# M_H_ext_disp.net
KiCad netlist of a schematic drawn in EAGLE
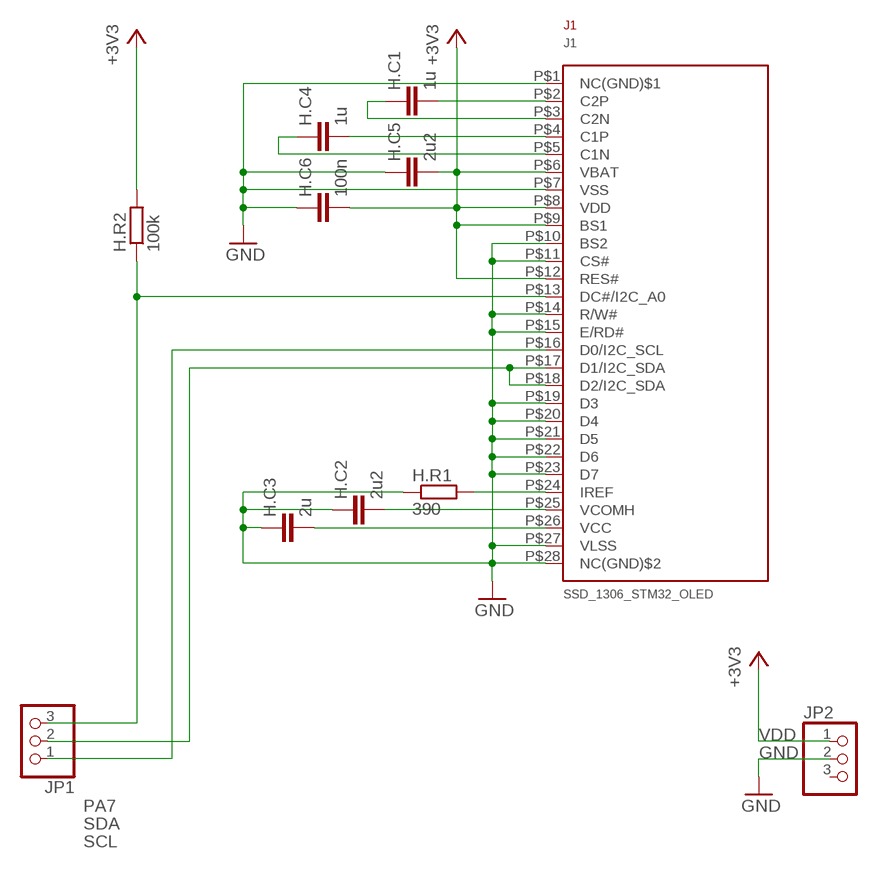
[diagram p0: schematic, sheet 1]

(export (version "E")
  (design (tool "Eeschema 10.0.6"))
  (components
    (comp (ref "H.C1")
      (value "1u")
      (footprint "eagle-import:C0603")
      (libsource (lib "eagle-import") (part "C-EUC0603"))
    )
    (comp (ref "H.C2")
      (value "2u2")
      (footprint "eagle-import:C0603")
      (libsource (lib "eagle-import") (part "C-EUC0603"))
    )
    (comp (ref "H.C3")
      (value "2u")
      (footprint "eagle-import:C0603")
      (libsource (lib "eagle-import") (part "C-EUC0603"))
    )
    (comp (ref "H.C4")
      (value "1u")
      (footprint "eagle-import:C0603")
      (libsource (lib "eagle-import") (part "C-EUC0603"))
    )
    (comp (ref "H.C5")
      (value "2u2")
      (footprint "eagle-import:C0603")
      (libsource (lib "eagle-import") (part "C-EUC0603"))
    )
    (comp (ref "H.C6")
      (value "100n")
      (footprint "eagle-import:C0603")
      (libsource (lib "eagle-import") (part "C-EUC0603"))
    )
    (comp (ref "H.R1")
      (value "390")
      (footprint "eagle-import:R0603")
      (libsource (lib "eagle-import") (part "R-EU_R0603"))
    )
    (comp (ref "H.R2")
      (value "100k")
      (footprint "eagle-import:R0603")
      (libsource (lib "eagle-import") (part "R-EU_R0603"))
    )
    (comp (ref "J1")
      (value "SSD_1306_STM32_OLED")
      (footprint "eagle-import:SSD_1306_STM32_OLED")
      (libsource (lib "eagle-import") (part "SSD_1306_STM32_OLED"))
    )
    (comp (ref "JP1")
      (value "PINHD-1X3")
      (footprint "eagle-import:1X03")
      (libsource (lib "eagle-import") (part "PINHD-1X3"))
    )
    (comp (ref "JP2")
      (value "PINHD-1X3")
      (footprint "eagle-import:1X03")
      (libsource (lib "eagle-import") (part "PINHD-1X3"))
    )
  )
  (nets
    (net (code "1") (name "+3V3") (class "Default")
      (node (ref "H.C5") (pin "2") (pinfunction "2_2") (pintype "passive"))
      (node (ref "H.C6") (pin "2") (pinfunction "2_2") (pintype "passive"))
      (node (ref "H.R2") (pin "2") (pinfunction "2_2") (pintype "passive"))
      (node (ref "J1") (pin "P$12") (pinfunction "RES#_P$12") (pintype "input"))
      (node (ref "J1") (pin "P$6") (pinfunction "VBAT_P$6") (pintype "input"))
      (node (ref "J1") (pin "P$8") (pinfunction "VDD_P$8") (pintype "power_in"))
      (node (ref "J1") (pin "P$9") (pinfunction "BS1_P$9") (pintype "input"))
      (node (ref "JP2") (pin "1") (pinfunction "1_1") (pintype "passive"))
    )
    (net (code "2") (name "/PA7") (class "Default")
      (node (ref "H.R2") (pin "1") (pinfunction "1_1") (pintype "passive"))
      (node (ref "J1") (pin "P$13") (pinfunction "DC#/I2C_A0_P$13") (pintype "input"))
      (node (ref "JP1") (pin "3") (pinfunction "3_3") (pintype "passive"))
    )
    (net (code "3") (name "/SCL") (class "Default")
      (node (ref "J1") (pin "P$16") (pinfunction "D0/I2C_SCL_P$16") (pintype "bidirectional"))
      (node (ref "JP1") (pin "1") (pinfunction "1_1") (pintype "passive"))
    )
    (net (code "4") (name "/SDA") (class "Default")
      (node (ref "J1") (pin "P$17") (pinfunction "D1/I2C_SDA_P$17") (pintype "bidirectional"))
      (node (ref "J1") (pin "P$18") (pinfunction "D2/I2C_SDA_P$18") (pintype "bidirectional"))
      (node (ref "JP1") (pin "2") (pinfunction "2_2") (pintype "passive"))
    )
    (net (code "5") (name "GND") (class "Default")
      (node (ref "H.C2") (pin "1") (pinfunction "1_1") (pintype "passive"))
      (node (ref "H.C3") (pin "1") (pinfunction "1_1") (pintype "passive"))
      (node (ref "H.C5") (pin "1") (pinfunction "1_1") (pintype "passive"))
      (node (ref "H.C6") (pin "1") (pinfunction "1_1") (pintype "passive"))
      (node (ref "H.R1") (pin "1") (pinfunction "1_1") (pintype "passive"))
      (node (ref "J1") (pin "P$1") (pinfunction "NC(GND)$1_P$1") (pintype "input"))
      (node (ref "J1") (pin "P$10") (pinfunction "BS2_P$10") (pintype "input"))
      (node (ref "J1") (pin "P$11") (pinfunction "CS#_P$11") (pintype "input"))
      (node (ref "J1") (pin "P$14") (pinfunction "R/W#_P$14") (pintype "input"))
      (node (ref "J1") (pin "P$15") (pinfunction "E/RD#_P$15") (pintype "input"))
      (node (ref "J1") (pin "P$19") (pinfunction "D3_P$19") (pintype "bidirectional"))
      (node (ref "J1") (pin "P$20") (pinfunction "D4_P$20") (pintype "bidirectional"))
      (node (ref "J1") (pin "P$21") (pinfunction "D5_P$21") (pintype "bidirectional"))
      (node (ref "J1") (pin "P$22") (pinfunction "D6_P$22") (pintype "bidirectional"))
      (node (ref "J1") (pin "P$23") (pinfunction "D7_P$23") (pintype "bidirectional"))
      (node (ref "J1") (pin "P$27") (pinfunction "VLSS_P$27") (pintype "power_in"))
      (node (ref "J1") (pin "P$28") (pinfunction "NC(GND)$2_P$28") (pintype "input"))
      (node (ref "J1") (pin "P$7") (pinfunction "VSS_P$7") (pintype "power_in"))
      (node (ref "JP2") (pin "2") (pinfunction "2_2") (pintype "passive"))
    )
    (net (code "6") (name "Net-(J1-C1N)") (class "Default")
      (node (ref "H.C4") (pin "1") (pinfunction "1_1") (pintype "passive"))
      (node (ref "J1") (pin "P$5") (pinfunction "C1N_P$5") (pintype "input"))
    )
    (net (code "7") (name "Net-(J1-C1P)") (class "Default")
      (node (ref "H.C4") (pin "2") (pinfunction "2_2") (pintype "passive"))
      (node (ref "J1") (pin "P$4") (pinfunction "C1P_P$4") (pintype "input"))
    )
    (net (code "8") (name "Net-(J1-C2N)") (class "Default")
      (node (ref "H.C1") (pin "1") (pinfunction "1_1") (pintype "passive"))
      (node (ref "J1") (pin "P$3") (pinfunction "C2N_P$3") (pintype "input"))
    )
    (net (code "9") (name "Net-(J1-C2P)") (class "Default")
      (node (ref "H.C1") (pin "2") (pinfunction "2_2") (pintype "passive"))
      (node (ref "J1") (pin "P$2") (pinfunction "C2P_P$2") (pintype "input"))
    )
    (net (code "10") (name "Net-(J1-IREF)") (class "Default")
      (node (ref "H.R1") (pin "2") (pinfunction "2_2") (pintype "passive"))
      (node (ref "J1") (pin "P$24") (pinfunction "IREF_P$24") (pintype "input"))
    )
    (net (code "11") (name "Net-(J1-VCC)") (class "Default")
      (node (ref "H.C3") (pin "2") (pinfunction "2_2") (pintype "passive"))
      (node (ref "J1") (pin "P$26") (pinfunction "VCC_P$26") (pintype "power_in"))
    )
    (net (code "12") (name "Net-(J1-VCOMH)") (class "Default")
      (node (ref "H.C2") (pin "2") (pinfunction "2_2") (pintype "passive"))
      (node (ref "J1") (pin "P$25") (pinfunction "VCOMH_P$25") (pintype "output"))
    )
    (net (code "13") (name "unconnected-(JP2-Pad3)") (class "Default")
      (node (ref "JP2") (pin "3") (pinfunction "3_3") (pintype "passive"))
    )
  )
)
